# LED.net
KiCad netlist of a schematic drawn in Altium Designer
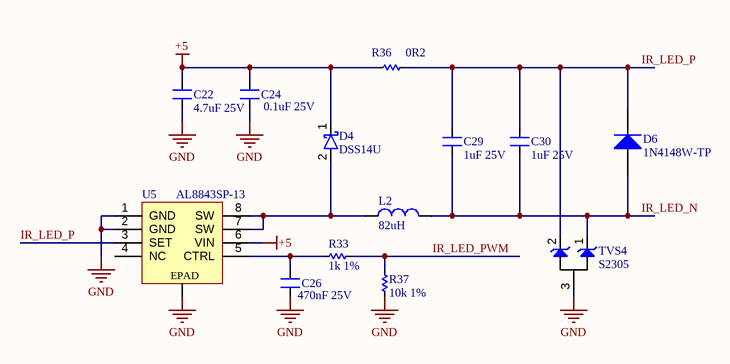
[diagram p0: LED.SchDoc]

(export (version "E")
  (design (tool "Eeschema 10.0.6"))
  (components
    (comp (ref "C22")
      (value "4.7uF 25V")
      (footprint "CN-SMD-0603-EXP-V101")
      (libsource (lib "Sang_library") (part "Capacitors"))
    )
    (comp (ref "C24")
      (value "0.1uF 25V")
      (footprint "CN-SMD-0603-EXP-V101")
      (libsource (lib "Sang_library") (part "Capacitors"))
    )
    (comp (ref "C26")
      (value "470nF 25V")
      (footprint "CN-SMD-0603-EXP-V101")
      (libsource (lib "Sang_library") (part "Capacitors"))
    )
    (comp (ref "C29")
      (value "1uF 25V")
      (footprint "CN-SMD-0603-EXP-V101")
      (libsource (lib "Sang_library") (part "Capacitors"))
    )
    (comp (ref "C30")
      (value "1uF 25V")
      (footprint "CN-SMD-0603-EXP-V101")
      (libsource (lib "Sang_library") (part "Capacitors"))
    )
    (comp (ref "D4")
      (value "DSS14U")
      (footprint "SOD-123-EXP-V101")
      (libsource (lib "Sang_library") (part "DSS14U"))
    )
    (comp (ref "D6")
      (value "1N4148W-TP")
      (footprint "SOD-123-EXP-V101")
      (description "DIODE GEN PURP 100V 300MA SOD123")
      (fields (field (name "MPN") "1N4148W-7-F") (field (name "MFR") "Diodes Incorporated"))
      (libsource (lib "EXP_V1") (part "1N4148W-TP"))
    )
    (comp (ref "L2")
      (value "82uH")
      (footprint "L-SMD-M-4.8x4.8x2.8mm")
      (description "SRR4828A-820M")
      (fields
        (field (name "PARTNO") "78477010")
        (field (name "MANUFACTURER") "Wurth Elektronik")
        (field (name "CREATED BY") "Baojun Chen")
      )
      (libsource (lib "Sang_library") (part "L-SMD-1"))
    )
    (comp (ref "R33")
      (value "1k 1%")
      (footprint "RES-SMD-0603-EXP-V101")
      (description "SMD")
      (fields
        (field (name "MANUFACTURER") "Generic Components")
        (field (name "PUBLISHER") "Altium Hobart Technology Centre")
      )
      (libsource (lib "Sang_library") (part "Res SMD"))
    )
    (comp (ref "R36")
      (value "0R2")
      (footprint "RES-SMD-1206-EXP-V101")
      (description "RES 0.1 OHM 1% 1W 1206\r\nPN: PE1206FRF470R1L")
      (fields
        (field (name "MANUFACTURER") "Generic Components")
        (field (name "PUBLISHER") "Altium Hobart Technology Centre")
      )
      (libsource (lib "Library") (part "Res-SMD"))
    )
    (comp (ref "R37")
      (value "10k 1%")
      (footprint "RES-SMD-0603-EXP-V101")
      (description "SMD")
      (fields
        (field (name "MANUFACTURER") "Generic Components")
        (field (name "PUBLISHER") "Altium Hobart Technology Centre")
      )
      (libsource (lib "Sang_library") (part "Res SMD"))
    )
    (comp (ref "TVS4")
      (value "S2305")
      (footprint "sot23-12_3")
      (description "TVS DIODE 5VWM 10.8VC SOT23")
      (libsource (lib "Sang_library") (part "S2305"))
    )
    (comp (ref "U5")
      (value "AL8843SP-13")
      (footprint "SO8_EPAD")
      (description "IC LED DRIVER RGLTR PWM 3A 8SO")
      (libsource (lib "Sang_library") (part "AL8843SP-13"))
    )
  )
  (nets
    (net (code "1") (name "+5") (class "Default")
      (node (ref "C22") (pin "2") (pinfunction "2_2") (pintype "passive"))
      (node (ref "C24") (pin "2") (pinfunction "2_2") (pintype "passive"))
      (node (ref "D4") (pin "1") (pinfunction "1_1") (pintype "passive"))
      (node (ref "R36") (pin "2") (pinfunction "2_2") (pintype "passive"))
      (node (ref "U5") (pin "6") (pinfunction "VIN_6") (pintype "passive"))
    )
    (net (code "2") (name "/IR_LED_N") (class "Default")
      (node (ref "C29") (pin "1") (pinfunction "1_1") (pintype "passive"))
      (node (ref "C30") (pin "1") (pinfunction "1_1") (pintype "passive"))
      (node (ref "D6") (pin "2") (pinfunction "A_2") (pintype "passive"))
      (node (ref "L2") (pin "2") (pinfunction "2_2") (pintype "passive"))
      (node (ref "TVS4") (pin "1") (pinfunction "1_1") (pintype "passive"))
    )
    (net (code "3") (name "/IR_LED_P") (class "Default")
      (node (ref "C29") (pin "2") (pinfunction "2_2") (pintype "passive"))
      (node (ref "C30") (pin "2") (pinfunction "2_2") (pintype "passive"))
      (node (ref "D6") (pin "1") (pinfunction "K_1") (pintype "passive"))
      (node (ref "R36") (pin "1") (pinfunction "1_1") (pintype "passive"))
      (node (ref "TVS4") (pin "2") (pinfunction "2_2") (pintype "passive"))
      (node (ref "U5") (pin "3") (pinfunction "SET_3") (pintype "passive"))
    )
    (net (code "4") (name "/IR_LED_PWM") (class "Default")
      (node (ref "R33") (pin "2") (pinfunction "2_2") (pintype "passive"))
      (node (ref "R37") (pin "2") (pinfunction "2_2") (pintype "passive"))
    )
    (net (code "5") (name "GND") (class "Default")
      (node (ref "C22") (pin "1") (pinfunction "1_1") (pintype "passive"))
      (node (ref "C24") (pin "1") (pinfunction "1_1") (pintype "passive"))
      (node (ref "C26") (pin "1") (pinfunction "1_1") (pintype "passive"))
      (node (ref "R37") (pin "1") (pinfunction "1_1") (pintype "passive"))
      (node (ref "TVS4") (pin "3") (pinfunction "3_3") (pintype "passive"))
      (node (ref "U5") (pin "1") (pinfunction "GND_1") (pintype "passive"))
      (node (ref "U5") (pin "2") (pinfunction "GND_2") (pintype "passive"))
      (node (ref "U5") (pin "EPAD") (pinfunction "EPAD_EPAD") (pintype "passive"))
    )
    (net (code "6") (name "Net-(D4-Pad2)") (class "Default")
      (node (ref "D4") (pin "2") (pinfunction "2_2") (pintype "passive"))
      (node (ref "L2") (pin "1") (pinfunction "1_1") (pintype "passive"))
      (node (ref "U5") (pin "7") (pinfunction "SW_7") (pintype "passive"))
      (node (ref "U5") (pin "8") (pinfunction "SW_8") (pintype "passive"))
    )
    (net (code "7") (name "Net-(U5-CTRL)") (class "Default")
      (node (ref "C26") (pin "2") (pinfunction "2_2") (pintype "passive"))
      (node (ref "R33") (pin "1") (pinfunction "1_1") (pintype "passive"))
      (node (ref "U5") (pin "5") (pinfunction "CTRL_5") (pintype "passive"))
    )
    (net (code "8") (name "unconnected-(U5-NC-Pad4)") (class "Default")
      (node (ref "U5") (pin "4") (pinfunction "NC_4") (pintype "passive"))
    )
  )
)
